# Power_supply.net
KiCad netlist of a schematic drawn in Altium Designer
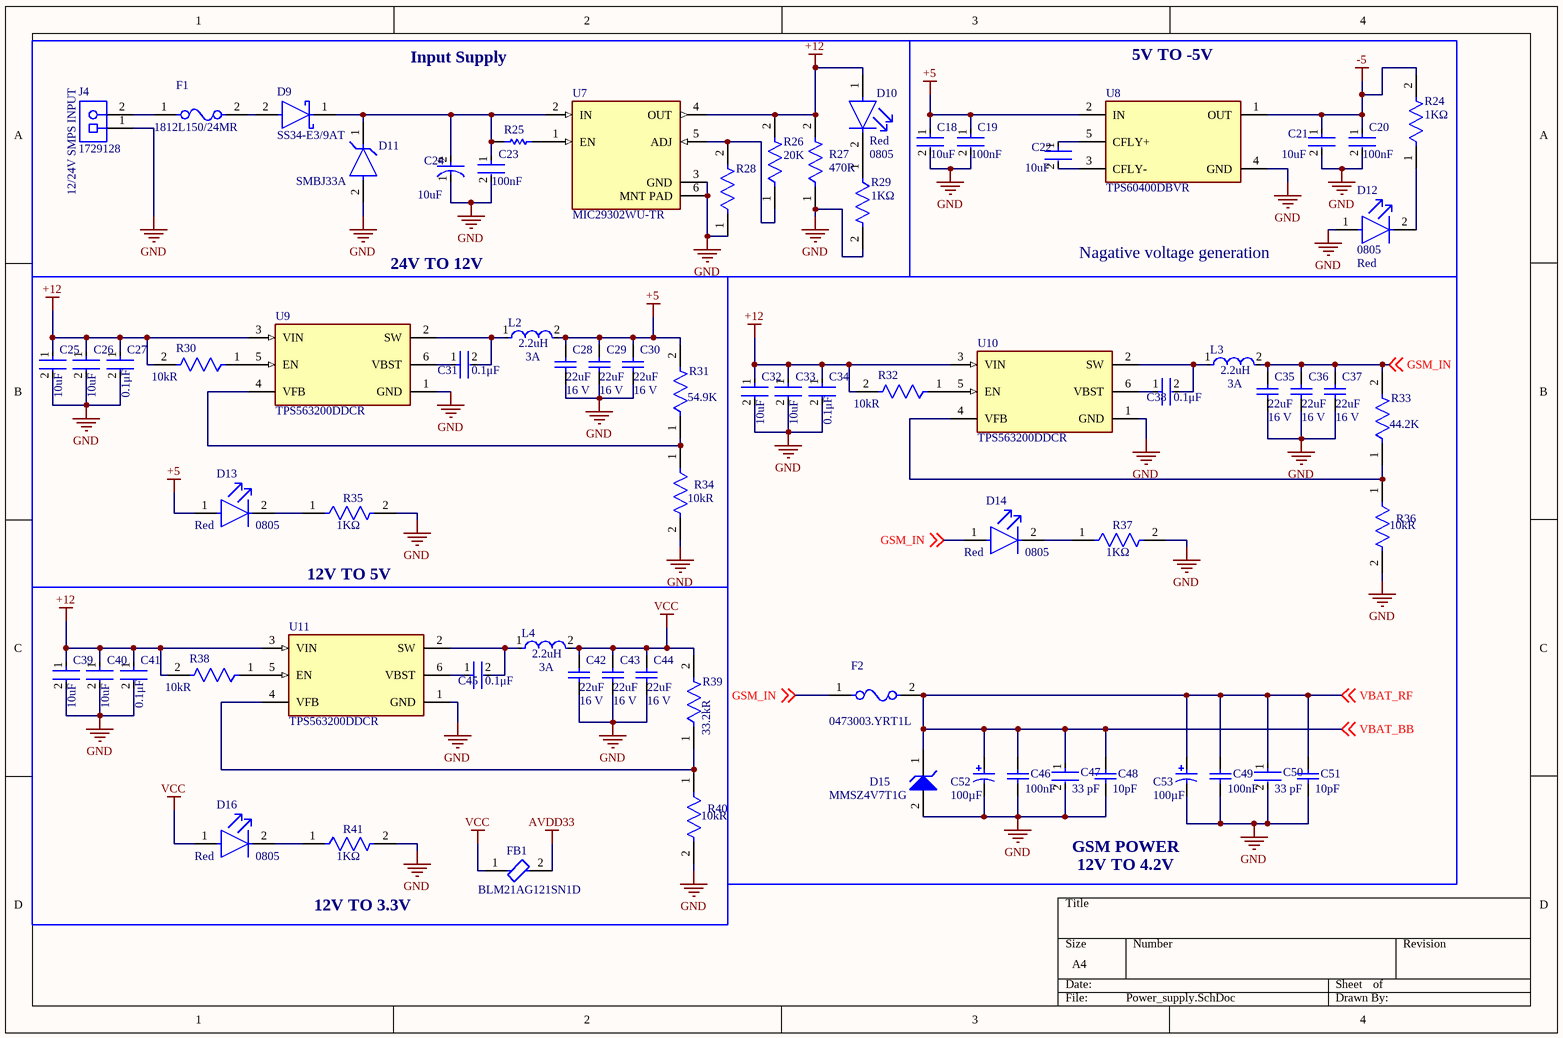
[diagram p0: Power_supply.SchDoc]

(export (version "E")
  (design (tool "Eeschema 10.0.6"))
  (components
    (comp (ref "C18")
      (value "10uF")
      (footprint "FP-C0805C-DG-MFG")
      (description "CAP CER 10UF 10V X5R 0805")
      (fields (field (name "TOLERANCE") "10%") (field (name "MANUFACTURER PART NUMBER") "C0805C106K8PACTU"))
      (libsource (lib "Altium Content Vault") (part "11868f565c42a9108669ba33697ecf6"))
    )
    (comp (ref "C19")
      (value "08051C104K4T2A")
      (footprint "FP-0805-L_2_01_0_2-W_1_25-IPC_B")
      (description "Automotive Ceramic Capacitor, 0805, 100nF, 10%, X7R, 15%, 100V")
      (fields
        (field (name "TOLERANCE") "10%")
        (field (name "CAPACITANCE") "100nF")
        (field (name "VOLTAGE") "100V")
      )
      (libsource (lib "Altium Content Vault") (part "b4654b650e69147ec39a6b967a45e02"))
    )
    (comp (ref "C20")
      (value "08051C104K4T2A")
      (footprint "FP-0805-L_2_01_0_2-W_1_25-IPC_B")
      (description "Automotive Ceramic Capacitor, 0805, 100nF, 10%, X7R, 15%, 100V")
      (fields
        (field (name "TOLERANCE") "10%")
        (field (name "CAPACITANCE") "100nF")
        (field (name "VOLTAGE") "100V")
      )
      (libsource (lib "Altium Content Vault") (part "b4654b650e69147ec39a6b967a45e02"))
    )
    (comp (ref "C21")
      (value "10uF")
      (footprint "FP-C0805C-DG-MFG")
      (description "CAP CER 10UF 10V X5R 0805")
      (fields (field (name "TOLERANCE") "10%") (field (name "MANUFACTURER PART NUMBER") "C0805C106K8PACTU"))
      (libsource (lib "Altium Content Vault") (part "11868f565c42a9108669ba33697ecf6"))
    )
    (comp (ref "C22")
      (value "10uF")
      (footprint "FP-C0805C-DG-MFG")
      (description "CAP CER 10UF 10V X5R 0805")
      (fields (field (name "TOLERANCE") "10%") (field (name "MANUFACTURER PART NUMBER") "C0805C106K8PACTU"))
      (libsource (lib "Altium Content Vault") (part "11868f565c42a9108669ba33697ecf6"))
    )
    (comp (ref "C23")
      (value "08051C104K4T2A")
      (footprint "FP-0805-L_2_01_0_2-W_1_25-IPC_B")
      (description "Automotive Ceramic Capacitor, 0805, 100nF, 10%, X7R, 15%, 100V")
      (fields
        (field (name "TOLERANCE") "10%")
        (field (name "CAPACITANCE") "100nF")
        (field (name "VOLTAGE") "100V")
      )
      (libsource (lib "Altium Content Vault") (part "b4654b650e69147ec39a6b967a45e02"))
    )
    (comp (ref "C24")
      (value "EEE-HA1H100P")
      (footprint "FP-HAD-MFG")
      (description "CAP ALUM 10UF 20% 50V SMD")
      (fields
        (field (name "TOLERANCE") "20%")
        (field (name "CAPACITANCE") "10uF")
        (field (name "VOLTAGE") "50V")
      )
      (libsource (lib "Altium Content Vault") (part "203bc49f2ac43e59fd269a8c329ed05"))
    )
    (comp (ref "C25")
      (value "10uF")
      (footprint "FP-C1206C-EH-MFG")
      (description "CAP CER 10UF 25V X7R 1206")
      (fields
        (field (name "MANUFACTURER PART NUMBER") "C1206C106K3RACAUTO")
        (field (name "OCTOPART") "https://octopart.com/c1206c106k3racauto-kemet-65707106")
      )
      (libsource (lib "Altium Content Vault") (part "11868f565c42a9108669ba33697ecf6"))
    )
    (comp (ref "C26")
      (value "10uF")
      (footprint "FP-C1206C-EH-MFG")
      (description "CAP CER 10UF 25V X7R 1206")
      (fields
        (field (name "MANUFACTURER PART NUMBER") "C1206C106K3RACAUTO")
        (field (name "OCTOPART") "https://octopart.com/c1206c106k3racauto-kemet-65707106")
      )
      (libsource (lib "Altium Content Vault") (part "11868f565c42a9108669ba33697ecf6"))
    )
    (comp (ref "C27")
      (value "0.1μF")
      (footprint "FP-C1206C-EB-MFG")
      (description "C1206 0.10 μF C0G 1.00% 25 V")
      (fields
        (field (name "MANUFACTURER PART NUMBER") "C1206C104F3GACAUTO")
        (field (name "OCTOPART") "https://octopart.com/c1206c104f3gacauto-kemet-88859926")
      )
      (libsource (lib "Altium Content Vault") (part "b4654b650e69147ec39a6b967a45e02"))
    )
    (comp (ref "C28")
      (value "22uF")
      (footprint "CAPC1206(3216)190_L")
      (description "CAP 22uF 16V -20% to +80% 1206 (3216 Metric) Thickness 1.9mm SMD")
      (fields
        (field (name "RATED VOLTAGE") "16 V")
        (field (name "TOLERANCE") "-20% to +80%")
        (field (name "Comment") "CAP 22uF 16V 1206(3216)")
      )
      (libsource (lib "Altium Content Vault") (part "CAP"))
    )
    (comp (ref "C29")
      (value "22uF")
      (footprint "CAPC1206(3216)190_L")
      (description "CAP 22uF 16V -20% to +80% 1206 (3216 Metric) Thickness 1.9mm SMD")
      (fields
        (field (name "RATED VOLTAGE") "16 V")
        (field (name "TOLERANCE") "-20% to +80%")
        (field (name "Comment") "CAP 22uF 16V 1206(3216)")
      )
      (libsource (lib "Altium Content Vault") (part "CAP"))
    )
    (comp (ref "C30")
      (value "22uF")
      (footprint "CAPC1206(3216)190_L")
      (description "CAP 22uF 16V -20% to +80% 1206 (3216 Metric) Thickness 1.9mm SMD")
      (fields
        (field (name "RATED VOLTAGE") "16 V")
        (field (name "TOLERANCE") "-20% to +80%")
        (field (name "Comment") "CAP 22uF 16V 1206(3216)")
      )
      (libsource (lib "Altium Content Vault") (part "CAP"))
    )
    (comp (ref "C31")
      (value "0.1μF")
      (footprint "FP-C1206C-EB-MFG")
      (description "C1206 0.10 μF C0G 1.00% 25 V")
      (fields
        (field (name "MANUFACTURER PART NUMBER") "C1206C104F3GACAUTO")
        (field (name "OCTOPART") "https://octopart.com/c1206c104f3gacauto-kemet-88859926")
      )
      (libsource (lib "Altium Content Vault") (part "b4654b650e69147ec39a6b967a45e02"))
    )
    (comp (ref "C32")
      (value "10uF")
      (footprint "FP-C1206C-EH-MFG")
      (description "CAP CER 10UF 25V X7R 1206")
      (fields
        (field (name "MANUFACTURER PART NUMBER") "C1206C106K3RACAUTO")
        (field (name "OCTOPART") "https://octopart.com/c1206c106k3racauto-kemet-65707106")
      )
      (libsource (lib "Altium Content Vault") (part "11868f565c42a9108669ba33697ecf6"))
    )
    (comp (ref "C33")
      (value "10uF")
      (footprint "FP-C1206C-EH-MFG")
      (description "CAP CER 10UF 25V X7R 1206")
      (fields
        (field (name "MANUFACTURER PART NUMBER") "C1206C106K3RACAUTO")
        (field (name "OCTOPART") "https://octopart.com/c1206c106k3racauto-kemet-65707106")
      )
      (libsource (lib "Altium Content Vault") (part "11868f565c42a9108669ba33697ecf6"))
    )
    (comp (ref "C34")
      (value "0.1μF")
      (footprint "FP-C1206C-EB-MFG")
      (description "C1206 0.10 μF C0G 1.00% 25 V")
      (fields
        (field (name "MANUFACTURER PART NUMBER") "C1206C104F3GACAUTO")
        (field (name "OCTOPART") "https://octopart.com/c1206c104f3gacauto-kemet-88859926")
      )
      (libsource (lib "Altium Content Vault") (part "b4654b650e69147ec39a6b967a45e02"))
    )
    (comp (ref "C35")
      (value "22uF")
      (footprint "CAPC1206(3216)190_L")
      (description "CAP 22uF 16V -20% to +80% 1206 (3216 Metric) Thickness 1.9mm SMD")
      (fields
        (field (name "RATED VOLTAGE") "16 V")
        (field (name "TOLERANCE") "-20% to +80%")
        (field (name "Comment") "CAP 22uF 16V 1206(3216)")
      )
      (libsource (lib "Altium Content Vault") (part "CAP"))
    )
    (comp (ref "C36")
      (value "22uF")
      (footprint "CAPC1206(3216)190_L")
      (description "CAP 22uF 16V -20% to +80% 1206 (3216 Metric) Thickness 1.9mm SMD")
      (fields
        (field (name "RATED VOLTAGE") "16 V")
        (field (name "TOLERANCE") "-20% to +80%")
        (field (name "Comment") "CAP 22uF 16V 1206(3216)")
      )
      (libsource (lib "Altium Content Vault") (part "CAP"))
    )
    (comp (ref "C37")
      (value "22uF")
      (footprint "CAPC1206(3216)190_L")
      (description "CAP 22uF 16V -20% to +80% 1206 (3216 Metric) Thickness 1.9mm SMD")
      (fields
        (field (name "RATED VOLTAGE") "16 V")
        (field (name "TOLERANCE") "-20% to +80%")
        (field (name "Comment") "CAP 22uF 16V 1206(3216)")
      )
      (libsource (lib "Altium Content Vault") (part "CAP"))
    )
    (comp (ref "C38")
      (value "0.1μF")
      (footprint "FP-C1206C-EB-MFG")
      (description "C1206 0.10 μF C0G 1.00% 25 V")
      (fields
        (field (name "MANUFACTURER PART NUMBER") "C1206C104F3GACAUTO")
        (field (name "OCTOPART") "https://octopart.com/c1206c104f3gacauto-kemet-88859926")
      )
      (libsource (lib "Altium Content Vault") (part "b4654b650e69147ec39a6b967a45e02"))
    )
    (comp (ref "C39")
      (value "10uF")
      (footprint "FP-C1206C-EH-MFG")
      (description "CAP CER 10UF 25V X7R 1206")
      (fields
        (field (name "MANUFACTURER PART NUMBER") "C1206C106K3RACAUTO")
        (field (name "OCTOPART") "https://octopart.com/c1206c106k3racauto-kemet-65707106")
      )
      (libsource (lib "Altium Content Vault") (part "11868f565c42a9108669ba33697ecf6"))
    )
    (comp (ref "C40")
      (value "10uF")
      (footprint "FP-C1206C-EH-MFG")
      (description "CAP CER 10UF 25V X7R 1206")
      (fields
        (field (name "MANUFACTURER PART NUMBER") "C1206C106K3RACAUTO")
        (field (name "OCTOPART") "https://octopart.com/c1206c106k3racauto-kemet-65707106")
      )
      (libsource (lib "Altium Content Vault") (part "11868f565c42a9108669ba33697ecf6"))
    )
    (comp (ref "C41")
      (value "0.1μF")
      (footprint "FP-C1206C-EB-MFG")
      (description "C1206 0.10 μF C0G 1.00% 25 V")
      (fields
        (field (name "MANUFACTURER PART NUMBER") "C1206C104F3GACAUTO")
        (field (name "OCTOPART") "https://octopart.com/c1206c104f3gacauto-kemet-88859926")
      )
      (libsource (lib "Altium Content Vault") (part "b4654b650e69147ec39a6b967a45e02"))
    )
    (comp (ref "C42")
      (value "22uF")
      (footprint "CAPC1206(3216)190_L")
      (description "CAP 22uF 16V -20% to +80% 1206 (3216 Metric) Thickness 1.9mm SMD")
      (fields
        (field (name "RATED VOLTAGE") "16 V")
        (field (name "TOLERANCE") "-20% to +80%")
        (field (name "Comment") "CAP 22uF 16V 1206(3216)")
      )
      (libsource (lib "Altium Content Vault") (part "CAP"))
    )
    (comp (ref "C43")
      (value "22uF")
      (footprint "CAPC1206(3216)190_L")
      (description "CAP 22uF 16V -20% to +80% 1206 (3216 Metric) Thickness 1.9mm SMD")
      (fields
        (field (name "RATED VOLTAGE") "16 V")
        (field (name "TOLERANCE") "-20% to +80%")
        (field (name "Comment") "CAP 22uF 16V 1206(3216)")
      )
      (libsource (lib "Altium Content Vault") (part "CAP"))
    )
    (comp (ref "C44")
      (value "22uF")
      (footprint "CAPC1206(3216)190_L")
      (description "CAP 22uF 16V -20% to +80% 1206 (3216 Metric) Thickness 1.9mm SMD")
      (fields
        (field (name "RATED VOLTAGE") "16 V")
        (field (name "TOLERANCE") "-20% to +80%")
        (field (name "Comment") "CAP 22uF 16V 1206(3216)")
      )
      (libsource (lib "Altium Content Vault") (part "CAP"))
    )
    (comp (ref "C45")
      (value "0.1μF")
      (footprint "FP-C1206C-EB-MFG")
      (description "C1206 0.10 μF C0G 1.00% 25 V")
      (fields
        (field (name "MANUFACTURER PART NUMBER") "C1206C104F3GACAUTO")
        (field (name "OCTOPART") "https://octopart.com/c1206c104f3gacauto-kemet-88859926")
      )
      (libsource (lib "Altium Content Vault") (part "b4654b650e69147ec39a6b967a45e02"))
    )
    (comp (ref "C46")
      (value "100nF")
      (footprint "CAPC1206(3216)170_L")
      (description "CAP 100nF 16V ±20% 1206 (3216 Metric) Thickness 1.7mm SMD")
      (fields (field (name "TOLERANCE") "Â±20%") (field (name "Comment") "CAP 100nF 16V 1206(3216)"))
      (libsource (lib "Altium Content Vault") (part "CAP"))
    )
    (comp (ref "C47")
      (value "33 pF")
      (footprint "FP-C1206C-EB-MFG")
      (description "CAP CER 33PF 16V NP0 1206")
      (fields (field (name "TOLERANCE") "0.2") (field (name "MANUFACTURER PART NUMBER") "C1206C330M4GACTU"))
      (libsource (lib "Altium Content Vault") (part "b4654b650e69147ec39a6b967a45e02"))
    )
    (comp (ref "C48")
      (value "10pF")
      (footprint "CAPC1206(3216)100_N")
      (description "CAP 10pF 16V ±10% 1206 (3216 Metric) Thickness 1mm SMD")
      (fields (field (name "TOLERANCE") "Â±10%") (field (name "Comment") "CAP 10pF 16V 1206(3216)"))
      (libsource (lib "Altium Content Vault") (part "CAP"))
    )
    (comp (ref "C49")
      (value "100nF")
      (footprint "CAPC1206(3216)170_L")
      (description "CAP 100nF 16V ±20% 1206 (3216 Metric) Thickness 1.7mm SMD")
      (fields (field (name "TOLERANCE") "Â±20%") (field (name "Comment") "CAP 100nF 16V 1206(3216)"))
      (libsource (lib "Altium Content Vault") (part "CAP"))
    )
    (comp (ref "C50")
      (value "33 pF")
      (footprint "FP-C1206C-EB-MFG")
      (description "CAP CER 33PF 16V NP0 1206")
      (fields (field (name "TOLERANCE") "0.2") (field (name "MANUFACTURER PART NUMBER") "C1206C330M4GACTU"))
      (libsource (lib "Altium Content Vault") (part "b4654b650e69147ec39a6b967a45e02"))
    )
    (comp (ref "C51")
      (value "10pF")
      (footprint "CAPC1206(3216)100_N")
      (description "CAP 10pF 16V ±10% 1206 (3216 Metric) Thickness 1mm SMD")
      (fields (field (name "TOLERANCE") "Â±10%") (field (name "Comment") "CAP 10pF 16V 1206(3216)"))
      (libsource (lib "Altium Content Vault") (part "CAP"))
    )
    (comp (ref "C52")
      (value "EEEFK1C101P")
      (footprint "PNSC-EEEFK1C101P_L")
      (fields (field (name "MANUFACTURER") "Panasonic") (field (name "CAPACITANCE") "100µF"))
      (libsource (lib "Altium Content Vault") (part "CAP-P-2"))
    )
    (comp (ref "C53")
      (value "EEEFK1C101P")
      (footprint "PNSC-EEEFK1C101P_L")
      (fields (field (name "MANUFACTURER") "Panasonic") (field (name "CAPACITANCE") "100µF"))
      (libsource (lib "Altium Content Vault") (part "CAP-P-2"))
    )
    (comp (ref "D9")
      (value "SS34-E3/9AT")
      (footprint "FP-SMC-MFG")
      (description "DIODE SCHOTTKY 40V 3A DO214AB")
      (libsource (lib "Altium Content Vault") (part "c1678fac7984e62e0809fbf79c06691"))
    )
    (comp (ref "D10")
      (value "SML-LX0805SRC-TR")
      (footprint "FP-SML-LX0805SRC-TR-MFG")
      (description "LED RED CLEAR SMD")
      (fields (field (name "CASE/PACKAGE") "0805") (field (name "ILLUMINATION COLOR") "Red"))
      (libsource (lib "Altium Content Vault") (part "ab1c01a81903e929fc6c44469aada92"))
    )
    (comp (ref "D11")
      (value "SMBJ33A")
      (footprint "FP-SMBJ-MFG")
      (description "TVS DIODE 33V 53.3V DO214AA")
      (fields
        (field (name "MANUFACTURER") "Littelfuse Inc")
        (field (name "OCTOPART") "https://octopart.com/smbj33a-littelfuse-350829")
      )
      (libsource (lib "Altium Content Vault") (part "f813f71cba58e380607f5dd3caf9714"))
    )
    (comp (ref "D12")
      (value "SML-LX0805SRC-TR")
      (footprint "FP-SML-LX0805SRC-TR-MFG")
      (description "LED RED CLEAR SMD")
      (fields (field (name "CASE/PACKAGE") "0805") (field (name "ILLUMINATION COLOR") "Red"))
      (libsource (lib "Altium Content Vault") (part "ab1c01a81903e929fc6c44469aada92"))
    )
    (comp (ref "D13")
      (value "SML-LX0805SRC-TR")
      (footprint "FP-SML-LX0805SRC-TR-MFG")
      (description "LED RED CLEAR SMD")
      (fields (field (name "CASE/PACKAGE") "0805") (field (name "ILLUMINATION COLOR") "Red"))
      (libsource (lib "Altium Content Vault") (part "ab1c01a81903e929fc6c44469aada92"))
    )
    (comp (ref "D14")
      (value "SML-LX0805SRC-TR")
      (footprint "FP-SML-LX0805SRC-TR-MFG")
      (description "LED RED CLEAR SMD")
      (fields (field (name "CASE/PACKAGE") "0805") (field (name "ILLUMINATION COLOR") "Red"))
      (libsource (lib "Altium Content Vault") (part "ab1c01a81903e929fc6c44469aada92"))
    )
    (comp (ref "D15")
      (value "MMSZ4V7T1G")
      (footprint "ONSC-SOD-123-2-425-04_V")
      (description "Zener Voltage Regulator, 500 mW, 2-Pin SOD-123, Pb-Free, Tape and Reel")
      (fields (field (name "MANUFACTURER") "On Semiconductor"))
      (libsource (lib "Altium Content Vault") (part "ONSC-K1A2-2"))
    )
    (comp (ref "D16")
      (value "SML-LX0805SRC-TR")
      (footprint "FP-SML-LX0805SRC-TR-MFG")
      (description "LED RED CLEAR SMD")
      (fields (field (name "CASE/PACKAGE") "0805") (field (name "ILLUMINATION COLOR") "Red"))
      (libsource (lib "Altium Content Vault") (part "ab1c01a81903e929fc6c44469aada92"))
    )
    (comp (ref "F1")
      (value "1812L150/24MR")
      (footprint "FP-1812L-MFG")
      (description "PTC RESET FUSE 24V 1.5A 1812")
      (fields
        (field (name "MANUFACTURER") "Littelfuse Inc")
        (field (name "OCTOPART") "https://octopart.com/1812l150%2F24mr-littelfuse-7130198")
      )
      (libsource (lib "Altium Content Vault") (part "5bcf9b9f640e542cf0359d10258e979"))
    )
    (comp (ref "F2")
      (value "0473003.YRT1L")
      (footprint "FP-473-0")
      (description "FUSE BRD MNT 3A 125VAC/VDC AXIAL")
      (fields
        (field (name "OCTOPART") "https://octopart.com/0473003.yrt1l-littelfuse-561109")
        (field (name "MANUFACTURER") "Littelfuse")
      )
      (libsource (lib "Altium Content Vault") (part "5bcf9b9f640e542cf0359d10258e979"))
    )
    (comp (ref "FB1")
      (value "BLM21AG121SN1D")
      (footprint "FP-BLM21-0_2-t0_85-e0_5-IPC_A")
      (description "FERRITE BEAD 120 OHM 0805 1LN")
      (fields (field (name "TOLERANCE") "25%"))
      (libsource (lib "Altium Content Vault") (part "5f30dd21d616792df468990f7003faa"))
    )
    (comp (ref "J4")
      (value "1729128")
      (footprint "PHOE-1729128-2_V")
      (description "PCB Terminal Block, 13.5 A, 400 V, 2-Pin THD, RoHS, Bulk")
      (fields (field (name "MANUFACTURER") "Phoenix Contact"))
      (libsource (lib "Altium Content Vault") (part "CN-2P-F-R2"))
    )
    (comp (ref "L2")
      (value "IFSC1515AHER2R2M01")
      (footprint "FP-IFSC1515AH-MFG")
      (description "FIXED IND 2.2UH 3A 45 MOHM SMD")
      (fields
        (field (name "RMS CURRENT (IRMS)") "3A")
        (field (name "TOLERANCE") "20%")
        (field (name "INDUCTANCE") "2.2uH")
      )
      (libsource (lib "Altium Content Vault") (part "725321dda6339637d4d059423bc1c3c"))
    )
    (comp (ref "L3")
      (value "IFSC1515AHER2R2M01")
      (footprint "FP-IFSC1515AH-MFG")
      (description "FIXED IND 2.2UH 3A 45 MOHM SMD")
      (fields
        (field (name "RMS CURRENT (IRMS)") "3A")
        (field (name "TOLERANCE") "20%")
        (field (name "INDUCTANCE") "2.2uH")
      )
      (libsource (lib "Altium Content Vault") (part "725321dda6339637d4d059423bc1c3c"))
    )
    (comp (ref "L4")
      (value "IFSC1515AHER2R2M01")
      (footprint "FP-IFSC1515AH-MFG")
      (description "FIXED IND 2.2UH 3A 45 MOHM SMD")
      (fields
        (field (name "RMS CURRENT (IRMS)") "3A")
        (field (name "TOLERANCE") "20%")
        (field (name "INDUCTANCE") "2.2uH")
      )
      (libsource (lib "Altium Content Vault") (part "725321dda6339637d4d059423bc1c3c"))
    )
    (comp (ref "R24")
      (value "1KΩ")
      (footprint "FP-CRGCQ0603-IPC_C")
      (description "CRGCQ 0603 1K0 5%")
      (fields
        (field (name "MANUFACTURER") "TE Connectivity")
        (field (name "MANUFACTURER PART NUMBER") "CRGCQ0603J1K0")
      )
      (libsource (lib "Altium Content Vault") (part "1029c3af85768c4190bb7ad29bc67b5"))
    )
    (comp (ref "R25")
      (value "CRCW080551K0FKEA")
      (footprint "RESC2013X50X30NL20T20")
      (fields (field (name "MANUFACTURER") "Vishay Dale"))
      (libsource (lib "Altium Content Vault") (part "RES"))
    )
    (comp (ref "R26")
      (value "12K")
      (footprint "FP-RC0805-0_6-IPC_C")
      (description "RES 100K OHM 1% 1/8W 0805")
      (fields (field (name "TOLERANCE") "1%") (field (name "RESISTANCE") "20K"))
      (libsource (lib "Altium Content Vault") (part "1029c3af85768c4190bb7ad29bc67b5"))
    )
    (comp (ref "R27")
      (value "CRCW0805470RJNEAHP")
      (footprint "FP-CRCW0805-HPe3-MFG")
      (description "RES Thick Film, 470Ω, 5%, 0.5W, 200ppm/°C, 0805")
      (fields (field (name "TOLERANCE") "5%") (field (name "RESISTANCE") "470R"))
      (libsource (lib "Altium Content Vault") (part "1029c3af85768c4190bb7ad29bc67b5"))
    )
    (comp (ref "R28")
      (value "CR0805-FX-4702ELF")
      (footprint "FP-CR0805-IPC_C")
      (description "Thick Film Chip Resistors 0805 47kΩ 0.125W 1% 100ppm/°C")
      (fields (field (name "TOLERANCE") "1%"))
      (libsource (lib "Altium Content Vault") (part "1029c3af85768c4190bb7ad29bc67b5"))
    )
    (comp (ref "R29")
      (value "1KΩ")
      (footprint "FP-CRGCQ0603-IPC_C")
      (description "CRGCQ 0603 1K0 5%")
      (fields
        (field (name "MANUFACTURER") "TE Connectivity")
        (field (name "MANUFACTURER PART NUMBER") "CRGCQ0603J1K0")
      )
      (libsource (lib "Altium Content Vault") (part "1029c3af85768c4190bb7ad29bc67b5"))
    )
    (comp (ref "R30")
      (value "CRCW060310K0FKED")
      (footprint "FP-CRCW0603-e3-IPC_A")
      (description "RES Thick Film, 10kΩ, 1%, 0.1W, 100ppm/°C, 0603")
      (fields (field (name "TOLERANCE") "1%") (field (name "RESISTANCE") "10kR"))
      (libsource (lib "Altium Content Vault") (part "1029c3af85768c4190bb7ad29bc67b5"))
    )
    (comp (ref "R31")
      (value "CRCW060332K4FHEAP")
      (footprint "FP-CRCW0603-Pe3-IPC_B")
      (description "RES Thick Film, 32.4kΩ, 1%, 0.1W, 50ppm/°C, 0603")
      (fields (field (name "RESISTANCE") "54.9K") (field (name "TOLERANCE") "1%"))
      (libsource (lib "Altium Content Vault") (part "1029c3af85768c4190bb7ad29bc67b5"))
    )
    (comp (ref "R32")
      (value "CRCW060310K0FKED")
      (footprint "FP-CRCW0603-e3-IPC_A")
      (description "RES Thick Film, 10kΩ, 1%, 0.1W, 100ppm/°C, 0603")
      (fields (field (name "TOLERANCE") "1%") (field (name "RESISTANCE") "10kR"))
      (libsource (lib "Altium Content Vault") (part "1029c3af85768c4190bb7ad29bc67b5"))
    )
    (comp (ref "R33")
      (value "CRCW060332K4FHEAP")
      (footprint "FP-CRCW0603-Pe3-IPC_B")
      (description "RES Thick Film, 32.4kΩ, 1%, 0.1W, 50ppm/°C, 0603")
      (fields (field (name "RESISTANCE") "44.2K") (field (name "TOLERANCE") "1%"))
      (libsource (lib "Altium Content Vault") (part "1029c3af85768c4190bb7ad29bc67b5"))
    )
    (comp (ref "R34")
      (value "CRCW060310K0FKED")
      (footprint "FP-CRCW0603-e3-IPC_A")
      (description "RES Thick Film, 10kΩ, 1%, 0.1W, 100ppm/°C, 0603")
      (fields (field (name "TOLERANCE") "1%") (field (name "RESISTANCE") "10kR"))
      (libsource (lib "Altium Content Vault") (part "1029c3af85768c4190bb7ad29bc67b5"))
    )
    (comp (ref "R35")
      (value "1KΩ")
      (footprint "FP-CRGCQ0603-IPC_C")
      (description "CRGCQ 0603 1K0 5%")
      (fields
        (field (name "MANUFACTURER") "TE Connectivity")
        (field (name "MANUFACTURER PART NUMBER") "CRGCQ0603J1K0")
      )
      (libsource (lib "Altium Content Vault") (part "1029c3af85768c4190bb7ad29bc67b5"))
    )
    (comp (ref "R36")
      (value "CRCW060310K0FKED")
      (footprint "FP-CRCW0603-e3-IPC_A")
      (description "RES Thick Film, 10kΩ, 1%, 0.1W, 100ppm/°C, 0603")
      (fields (field (name "TOLERANCE") "1%") (field (name "RESISTANCE") "10kR"))
      (libsource (lib "Altium Content Vault") (part "1029c3af85768c4190bb7ad29bc67b5"))
    )
    (comp (ref "R37")
      (value "1KΩ")
      (footprint "FP-CRGCQ0603-IPC_C")
      (description "CRGCQ 0603 1K0 5%")
      (fields
        (field (name "MANUFACTURER") "TE Connectivity")
        (field (name "MANUFACTURER PART NUMBER") "CRGCQ0603J1K0")
      )
      (libsource (lib "Altium Content Vault") (part "1029c3af85768c4190bb7ad29bc67b5"))
    )
    (comp (ref "R38")
      (value "CRCW060310K0FKED")
      (footprint "FP-CRCW0603-e3-IPC_A")
      (description "RES Thick Film, 10kΩ, 1%, 0.1W, 100ppm/°C, 0603")
      (fields (field (name "TOLERANCE") "1%") (field (name "RESISTANCE") "10kR"))
      (libsource (lib "Altium Content Vault") (part "1029c3af85768c4190bb7ad29bc67b5"))
    )
    (comp (ref "R39")
      (value "CRCW060332K4FHEAP")
      (footprint "FP-CRCW0603-Pe3-IPC_B")
      (description "RES Thick Film, 32.4kΩ, 1%, 0.1W, 50ppm/°C, 0603")
      (fields (field (name "RESISTANCE") "33.2kR") (field (name "TOLERANCE") "1%"))
      (libsource (lib "Altium Content Vault") (part "1029c3af85768c4190bb7ad29bc67b5"))
    )
    (comp (ref "R40")
      (value "CRCW060310K0FKED")
      (footprint "FP-CRCW0603-e3-IPC_A")
      (description "RES Thick Film, 10kΩ, 1%, 0.1W, 100ppm/°C, 0603")
      (fields (field (name "TOLERANCE") "1%") (field (name "RESISTANCE") "10kR"))
      (libsource (lib "Altium Content Vault") (part "1029c3af85768c4190bb7ad29bc67b5"))
    )
    (comp (ref "R41")
      (value "1KΩ")
      (footprint "FP-CRGCQ0603-IPC_C")
      (description "CRGCQ 0603 1K0 5%")
      (fields
        (field (name "MANUFACTURER") "TE Connectivity")
        (field (name "MANUFACTURER PART NUMBER") "CRGCQ0603J1K0")
      )
      (libsource (lib "Altium Content Vault") (part "1029c3af85768c4190bb7ad29bc67b5"))
    )
    (comp (ref "U7")
      (value "MIC29302WU-TR")
      (footprint "FP-C04-012-MFG")
      (description "IC REG LINEAR POS ADJ 3A TO263-5")
      (fields
        (field (name "MANUFACTURER") "Microchip")
        (field (name "OCTOPART") "https://octopart.com/mic29302wu-tr-microchip-66801318")
      )
      (libsource (lib "Altium Content Vault") (part "0db40f55fda0e91d0d14528974a446d"))
    )
    (comp (ref "U8")
      (value "TPS60400DBVR")
      (footprint "FP-DBV0005A-IPC_C")
      (description "IC REG CHARG PUMP INV 60MA SOT23")
      (libsource (lib "Altium Content Vault") (part "027376aeb0d6df1338393bd3c828556"))
    )
    (comp (ref "U9")
      (value "TPS563200DDCR")
      (footprint "FP-DDC0006A-MFG")
      (description "IC REG BUCK ADJ 3A TSOT23-6")
      (libsource (lib "Altium Content Vault") (part "31d0a13bcb823f7fa58c78a9b473f81"))
    )
    (comp (ref "U10")
      (value "TPS563200DDCR")
      (footprint "FP-DDC0006A-MFG")
      (description "IC REG BUCK ADJ 3A TSOT23-6")
      (libsource (lib "Altium Content Vault") (part "31d0a13bcb823f7fa58c78a9b473f81"))
    )
    (comp (ref "U11")
      (value "TPS563200DDCR")
      (footprint "FP-DDC0006A-MFG")
      (description "IC REG BUCK ADJ 3A TSOT23-6")
      (libsource (lib "Altium Content Vault") (part "31d0a13bcb823f7fa58c78a9b473f81"))
    )
  )
  (nets
    (net (code "1") (name "+5") (class "Default")
      (node (ref "C18") (pin "1") (pinfunction "1_1") (pintype "passive"))
      (node (ref "C19") (pin "1") (pinfunction "1_1") (pintype "passive"))
      (node (ref "C28") (pin "2") (pinfunction "2_2") (pintype "passive"))
      (node (ref "C29") (pin "2") (pinfunction "2_2") (pintype "passive"))
      (node (ref "C30") (pin "2") (pinfunction "2_2") (pintype "passive"))
      (node (ref "D13") (pin "1") (pinfunction "A_1") (pintype "passive"))
      (node (ref "L2") (pin "2") (pinfunction "2_2") (pintype "passive"))
      (node (ref "R31") (pin "2") (pinfunction "2_2") (pintype "passive"))
      (node (ref "U8") (pin "2") (pinfunction "IN_2") (pintype "power_in"))
    )
    (net (code "2") (name "+12") (class "Default")
      (node (ref "C25") (pin "1") (pinfunction "1_1") (pintype "passive"))
      (node (ref "C26") (pin "1") (pinfunction "1_1") (pintype "passive"))
      (node (ref "C27") (pin "1") (pinfunction "1_1") (pintype "passive"))
      (node (ref "C32") (pin "1") (pinfunction "1_1") (pintype "passive"))
      (node (ref "C33") (pin "1") (pinfunction "1_1") (pintype "passive"))
      (node (ref "C34") (pin "1") (pinfunction "1_1") (pintype "passive"))
      (node (ref "C39") (pin "1") (pinfunction "1_1") (pintype "passive"))
      (node (ref "C40") (pin "1") (pinfunction "1_1") (pintype "passive"))
      (node (ref "C41") (pin "1") (pinfunction "1_1") (pintype "passive"))
      (node (ref "D10") (pin "1") (pinfunction "A_1") (pintype "passive"))
      (node (ref "R26") (pin "2") (pinfunction "2_2") (pintype "passive"))
      (node (ref "R27") (pin "2") (pinfunction "2_2") (pintype "passive"))
      (node (ref "R30") (pin "2") (pinfunction "2_2") (pintype "passive"))
      (node (ref "R32") (pin "2") (pinfunction "2_2") (pintype "passive"))
      (node (ref "R38") (pin "2") (pinfunction "2_2") (pintype "passive"))
      (node (ref "U10") (pin "3") (pinfunction "VIN_3") (pintype "input"))
      (node (ref "U11") (pin "3") (pinfunction "VIN_3") (pintype "input"))
      (node (ref "U7") (pin "4") (pinfunction "OUT_4") (pintype "output"))
      (node (ref "U9") (pin "3") (pinfunction "VIN_3") (pintype "input"))
    )
    (net (code "3") (name "-5") (class "Default")
      (node (ref "C20") (pin "1") (pinfunction "1_1") (pintype "passive"))
      (node (ref "C21") (pin "1") (pinfunction "1_1") (pintype "passive"))
      (node (ref "R24") (pin "2") (pinfunction "2_2") (pintype "passive"))
      (node (ref "U8") (pin "1") (pinfunction "OUT_1") (pintype "power_in"))
    )
    (net (code "4") (name "AVDD33") (class "Default")
      (node (ref "FB1") (pin "2") (pinfunction "2_2") (pintype "passive"))
    )
    (net (code "5") (name "GND") (class "Default")
      (node (ref "C18") (pin "2") (pinfunction "2_2") (pintype "passive"))
      (node (ref "C19") (pin "2") (pinfunction "2_2") (pintype "passive"))
      (node (ref "C20") (pin "2") (pinfunction "2_2") (pintype "passive"))
      (node (ref "C21") (pin "2") (pinfunction "2_2") (pintype "passive"))
      (node (ref "C23") (pin "2") (pinfunction "2_2") (pintype "passive"))
      (node (ref "C24") (pin "1") (pinfunction "C_1") (pintype "passive"))
      (node (ref "C25") (pin "2") (pinfunction "2_2") (pintype "passive"))
      (node (ref "C26") (pin "2") (pinfunction "2_2") (pintype "passive"))
      (node (ref "C27") (pin "2") (pinfunction "2_2") (pintype "passive"))
      (node (ref "C28") (pin "1") (pinfunction "1_1") (pintype "passive"))
      (node (ref "C29") (pin "1") (pinfunction "1_1") (pintype "passive"))
      (node (ref "C30") (pin "1") (pinfunction "1_1") (pintype "passive"))
      (node (ref "C32") (pin "2") (pinfunction "2_2") (pintype "passive"))
      (node (ref "C33") (pin "2") (pinfunction "2_2") (pintype "passive"))
      (node (ref "C34") (pin "2") (pinfunction "2_2") (pintype "passive"))
      (node (ref "C35") (pin "1") (pinfunction "1_1") (pintype "passive"))
      (node (ref "C36") (pin "1") (pinfunction "1_1") (pintype "passive"))
      (node (ref "C37") (pin "1") (pinfunction "1_1") (pintype "passive"))
      (node (ref "C39") (pin "2") (pinfunction "2_2") (pintype "passive"))
      (node (ref "C40") (pin "2") (pinfunction "2_2") (pintype "passive"))
      (node (ref "C41") (pin "2") (pinfunction "2_2") (pintype "passive"))
      (node (ref "C42") (pin "1") (pinfunction "1_1") (pintype "passive"))
      (node (ref "C43") (pin "1") (pinfunction "1_1") (pintype "passive"))
      (node (ref "C44") (pin "1") (pinfunction "1_1") (pintype "passive"))
      (node (ref "C46") (pin "1") (pinfunction "1_1") (pintype "passive"))
      (node (ref "C47") (pin "2") (pinfunction "2_2") (pintype "passive"))
      (node (ref "C48") (pin "1") (pinfunction "1_1") (pintype "passive"))
      (node (ref "C49") (pin "1") (pinfunction "1_1") (pintype "passive"))
      (node (ref "C50") (pin "2") (pinfunction "2_2") (pintype "passive"))
      (node (ref "C51") (pin "1") (pinfunction "1_1") (pintype "passive"))
      (node (ref "C52") (pin "2") (pinfunction "2_2") (pintype "passive"))
      (node (ref "C53") (pin "2") (pinfunction "2_2") (pintype "passive"))
      (node (ref "D11") (pin "2") (pinfunction "A_2") (pintype "passive"))
      (node (ref "D12") (pin "1") (pinfunction "A_1") (pintype "passive"))
      (node (ref "D15") (pin "2") (pinfunction "A_2") (pintype "passive"))
      (node (ref "J4") (pin "1") (pinfunction "1_1") (pintype "passive"))
      (node (ref "R27") (pin "1") (pinfunction "1_1") (pintype "passive"))
      (node (ref "R28") (pin "1") (pinfunction "1_1") (pintype "passive"))
      (node (ref "R29") (pin "2") (pinfunction "2_2") (pintype "passive"))
      (node (ref "R34") (pin "2") (pinfunction "2_2") (pintype "passive"))
      (node (ref "R35") (pin "2") (pinfunction "2_2") (pintype "passive"))
      (node (ref "R36") (pin "2") (pinfunction "2_2") (pintype "passive"))
      (node (ref "R37") (pin "2") (pinfunction "2_2") (pintype "passive"))
      (node (ref "R40") (pin "2") (pinfunction "2_2") (pintype "passive"))
      (node (ref "R41") (pin "2") (pinfunction "2_2") (pintype "passive"))
      (node (ref "U10") (pin "1") (pinfunction "GND_1") (pintype "power_in"))
      (node (ref "U11") (pin "1") (pinfunction "GND_1") (pintype "power_in"))
      (node (ref "U7") (pin "3") (pinfunction "GND_3") (pintype "power_in"))
      (node (ref "U7") (pin "6") (pinfunction "MNT_PAD_6") (pintype "passive"))
      (node (ref "U8") (pin "4") (pinfunction "GND_4") (pintype "power_in"))
      (node (ref "U9") (pin "1") (pinfunction "GND_1") (pintype "power_in"))
    )
    (net (code "6") (name "GSM_IN") (class "Default")
      (node (ref "C35") (pin "2") (pinfunction "2_2") (pintype "passive"))
      (node (ref "C36") (pin "2") (pinfunction "2_2") (pintype "passive"))
      (node (ref "C37") (pin "2") (pinfunction "2_2") (pintype "passive"))
      (node (ref "D14") (pin "1") (pinfunction "A_1") (pintype "passive"))
      (node (ref "F2") (pin "1") (pinfunction "1_1") (pintype "passive"))
      (node (ref "L3") (pin "2") (pinfunction "2_2") (pintype "passive"))
      (node (ref "R33") (pin "2") (pinfunction "2_2") (pintype "passive"))
    )
    (net (code "7") (name "Net-(C24-A)") (class "Default")
      (node (ref "C23") (pin "1") (pinfunction "1_1") (pintype "passive"))
      (node (ref "C24") (pin "2") (pinfunction "A_2") (pintype "passive"))
      (node (ref "D11") (pin "1") (pinfunction "C_1") (pintype "passive"))
      (node (ref "D9") (pin "1") (pinfunction "C_1") (pintype "passive"))
      (node (ref "R25") (pin "2") (pinfunction "2_2") (pintype "passive"))
      (node (ref "U7") (pin "2") (pinfunction "IN_2") (pintype "input"))
    )
    (net (code "8") (name "Net-(D9-A)") (class "Default")
      (node (ref "D9") (pin "2") (pinfunction "A_2") (pintype "passive"))
      (node (ref "F1") (pin "2") (pinfunction "2_2") (pintype "passive"))
    )
    (net (code "9") (name "Net-(D10-C)") (class "Default")
      (node (ref "D10") (pin "2") (pinfunction "C_2") (pintype "passive"))
      (node (ref "R29") (pin "1") (pinfunction "1_1") (pintype "passive"))
    )
    (net (code "10") (name "Net-(D12-C)") (class "Default")
      (node (ref "D12") (pin "2") (pinfunction "C_2") (pintype "passive"))
      (node (ref "R24") (pin "1") (pinfunction "1_1") (pintype "passive"))
    )
    (net (code "11") (name "Net-(D13-C)") (class "Default")
      (node (ref "D13") (pin "2") (pinfunction "C_2") (pintype "passive"))
      (node (ref "R35") (pin "1") (pinfunction "1_1") (pintype "passive"))
    )
    (net (code "12") (name "Net-(D14-C)") (class "Default")
      (node (ref "D14") (pin "2") (pinfunction "C_2") (pintype "passive"))
      (node (ref "R37") (pin "1") (pinfunction "1_1") (pintype "passive"))
    )
    (net (code "13") (name "Net-(D16-C)") (class "Default")
      (node (ref "D16") (pin "2") (pinfunction "C_2") (pintype "passive"))
      (node (ref "R41") (pin "1") (pinfunction "1_1") (pintype "passive"))
    )
    (net (code "14") (name "Net-(F1-Pad1)") (class "Default")
      (node (ref "F1") (pin "1") (pinfunction "1_1") (pintype "passive"))
      (node (ref "J4") (pin "2") (pinfunction "2_2") (pintype "passive"))
    )
    (net (code "15") (name "Net-(U7-ADJ)") (class "Default")
      (node (ref "R26") (pin "1") (pinfunction "1_1") (pintype "passive"))
      (node (ref "R28") (pin "2") (pinfunction "2_2") (pintype "passive"))
      (node (ref "U7") (pin "5") (pinfunction "ADJ_5") (pintype "input"))
    )
    (net (code "16") (name "Net-(U7-EN)") (class "Default")
      (node (ref "R25") (pin "1") (pinfunction "1_1") (pintype "passive"))
      (node (ref "U7") (pin "1") (pinfunction "EN_1") (pintype "input"))
    )
    (net (code "17") (name "Net-(U8-CFLY+)") (class "Default")
      (node (ref "C22") (pin "1") (pinfunction "1_1") (pintype "passive"))
      (node (ref "U8") (pin "5") (pinfunction "CFLY+_5") (pintype "passive"))
    )
    (net (code "18") (name "Net-(U8-CFLY-)") (class "Default")
      (node (ref "C22") (pin "2") (pinfunction "2_2") (pintype "passive"))
      (node (ref "U8") (pin "3") (pinfunction "CFLY-_3") (pintype "passive"))
    )
    (net (code "19") (name "Net-(U9-EN)") (class "Default")
      (node (ref "R30") (pin "1") (pinfunction "1_1") (pintype "passive"))
      (node (ref "U9") (pin "5") (pinfunction "EN_5") (pintype "input"))
    )
    (net (code "20") (name "Net-(U9-SW)") (class "Default")
      (node (ref "C31") (pin "2") (pinfunction "2_2") (pintype "passive"))
      (node (ref "L2") (pin "1") (pinfunction "1_1") (pintype "passive"))
      (node (ref "U9") (pin "2") (pinfunction "SW_2") (pintype "passive"))
    )
    (net (code "21") (name "Net-(U9-VBST)") (class "Default")
      (node (ref "C31") (pin "1") (pinfunction "1_1") (pintype "passive"))
      (node (ref "U9") (pin "6") (pinfunction "VBST_6") (pintype "passive"))
    )
    (net (code "22") (name "Net-(U9-VFB)") (class "Default")
      (node (ref "R31") (pin "1") (pinfunction "1_1") (pintype "passive"))
      (node (ref "R34") (pin "1") (pinfunction "1_1") (pintype "passive"))
      (node (ref "U9") (pin "4") (pinfunction "VFB_4") (pintype "passive"))
    )
    (net (code "23") (name "Net-(U10-EN)") (class "Default")
      (node (ref "R32") (pin "1") (pinfunction "1_1") (pintype "passive"))
      (node (ref "U10") (pin "5") (pinfunction "EN_5") (pintype "input"))
    )
    (net (code "24") (name "Net-(U10-SW)") (class "Default")
      (node (ref "C38") (pin "2") (pinfunction "2_2") (pintype "passive"))
      (node (ref "L3") (pin "1") (pinfunction "1_1") (pintype "passive"))
      (node (ref "U10") (pin "2") (pinfunction "SW_2") (pintype "passive"))
    )
    (net (code "25") (name "Net-(U10-VBST)") (class "Default")
      (node (ref "C38") (pin "1") (pinfunction "1_1") (pintype "passive"))
      (node (ref "U10") (pin "6") (pinfunction "VBST_6") (pintype "passive"))
    )
    (net (code "26") (name "Net-(U10-VFB)") (class "Default")
      (node (ref "R33") (pin "1") (pinfunction "1_1") (pintype "passive"))
      (node (ref "R36") (pin "1") (pinfunction "1_1") (pintype "passive"))
      (node (ref "U10") (pin "4") (pinfunction "VFB_4") (pintype "passive"))
    )
    (net (code "27") (name "Net-(U11-EN)") (class "Default")
      (node (ref "R38") (pin "1") (pinfunction "1_1") (pintype "passive"))
      (node (ref "U11") (pin "5") (pinfunction "EN_5") (pintype "input"))
    )
    (net (code "28") (name "Net-(U11-SW)") (class "Default")
      (node (ref "C45") (pin "2") (pinfunction "2_2") (pintype "passive"))
      (node (ref "L4") (pin "1") (pinfunction "1_1") (pintype "passive"))
      (node (ref "U11") (pin "2") (pinfunction "SW_2") (pintype "passive"))
    )
    (net (code "29") (name "Net-(U11-VBST)") (class "Default")
      (node (ref "C45") (pin "1") (pinfunction "1_1") (pintype "passive"))
      (node (ref "U11") (pin "6") (pinfunction "VBST_6") (pintype "passive"))
    )
    (net (code "30") (name "Net-(U11-VFB)") (class "Default")
      (node (ref "R39") (pin "1") (pinfunction "1_1") (pintype "passive"))
      (node (ref "R40") (pin "1") (pinfunction "1_1") (pintype "passive"))
      (node (ref "U11") (pin "4") (pinfunction "VFB_4") (pintype "passive"))
    )
    (net (code "31") (name "VBAT_BB") (class "Default")
      (node (ref "C46") (pin "2") (pinfunction "2_2") (pintype "passive"))
      (node (ref "C47") (pin "1") (pinfunction "1_1") (pintype "passive"))
      (node (ref "C48") (pin "2") (pinfunction "2_2") (pintype "passive"))
      (node (ref "C49") (pin "2") (pinfunction "2_2") (pintype "passive"))
      (node (ref "C50") (pin "1") (pinfunction "1_1") (pintype "passive"))
      (node (ref "C51") (pin "2") (pinfunction "2_2") (pintype "passive"))
      (node (ref "C52") (pin "1") (pinfunction "1_1") (pintype "passive"))
      (node (ref "C53") (pin "1") (pinfunction "1_1") (pintype "passive"))
      (node (ref "D15") (pin "1") (pinfunction "K_1") (pintype "passive"))
      (node (ref "F2") (pin "2") (pinfunction "2_2") (pintype "passive"))
    )
    (net (code "32") (name "VCC") (class "Default")
      (node (ref "C42") (pin "2") (pinfunction "2_2") (pintype "passive"))
      (node (ref "C43") (pin "2") (pinfunction "2_2") (pintype "passive"))
      (node (ref "C44") (pin "2") (pinfunction "2_2") (pintype "passive"))
      (node (ref "D16") (pin "1") (pinfunction "A_1") (pintype "passive"))
      (node (ref "FB1") (pin "1") (pinfunction "1_1") (pintype "passive"))
      (node (ref "L4") (pin "2") (pinfunction "2_2") (pintype "passive"))
      (node (ref "R39") (pin "2") (pinfunction "2_2") (pintype "passive"))
    )
  )
)
